# Center_Console_-_Inputs.net
KiCad netlist of a schematic drawn in Altium Designer
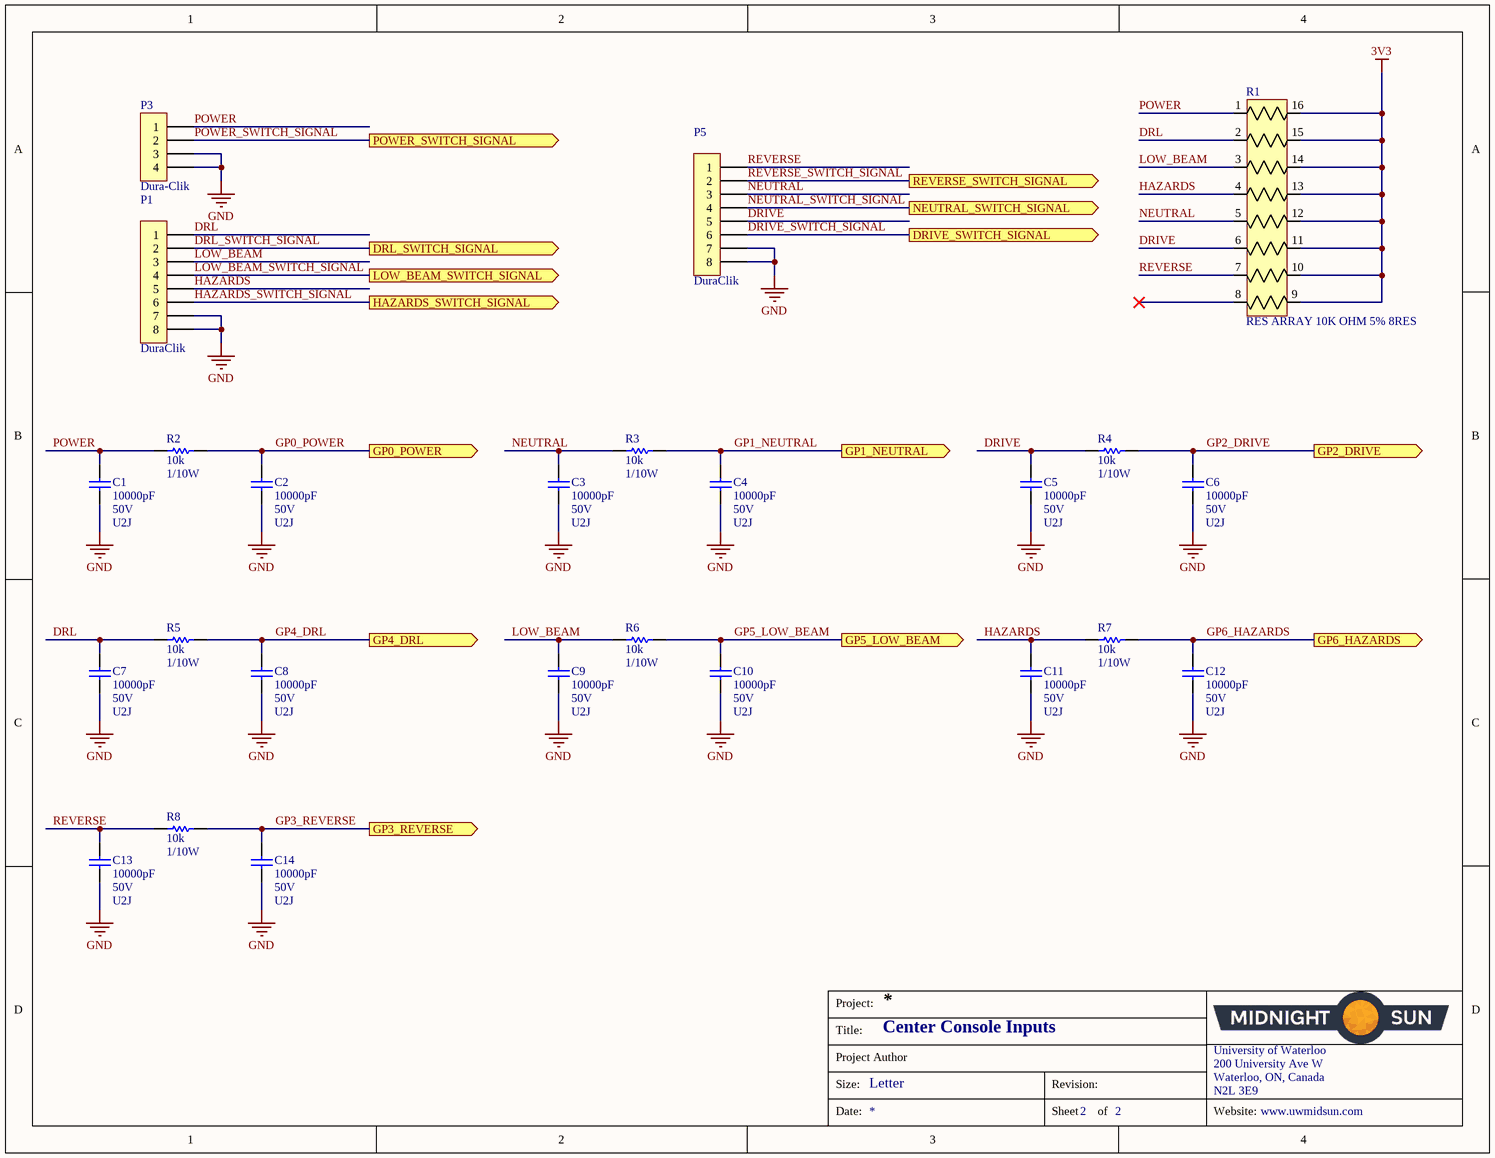
[diagram p0: Center Console - Inputs.SchDoc]

(export (version "E")
  (design (tool "Eeschema 10.0.6"))
  (components
    (comp (ref "C1")
      (value "CAP CER 10nF 50V 5% X7R 0603")
      (footprint "CAP, 0603")
      (description "10000pF ±5% 50V Ceramic Capacitor U2J 0603 (1608 Metric)")
      (fields
        (field (name "TOLERANCE") "±5%")
        (field (name "CAPACITANCE") "10000pF")
        (field (name "VOLTAGE") "50V")
        (field (name "TEMPERATURE COEFFICIENT") "U2J")
      )
      (libsource (lib "Schematic Diagrams") (part "CAP CER 10nF 50V 5% X7R 0603"))
    )
    (comp (ref "C2")
      (value "CAP CER 10nF 50V 5% X7R 0603")
      (footprint "CAP, 0603")
      (description "10000pF ±5% 50V Ceramic Capacitor U2J 0603 (1608 Metric)")
      (fields
        (field (name "TOLERANCE") "±5%")
        (field (name "CAPACITANCE") "10000pF")
        (field (name "VOLTAGE") "50V")
        (field (name "TEMPERATURE COEFFICIENT") "U2J")
      )
      (libsource (lib "Schematic Diagrams") (part "CAP CER 10nF 50V 5% X7R 0603"))
    )
    (comp (ref "C3")
      (value "CAP CER 10nF 50V 5% X7R 0603")
      (footprint "CAP, 0603")
      (description "10000pF ±5% 50V Ceramic Capacitor U2J 0603 (1608 Metric)")
      (fields
        (field (name "TOLERANCE") "±5%")
        (field (name "CAPACITANCE") "10000pF")
        (field (name "VOLTAGE") "50V")
        (field (name "TEMPERATURE COEFFICIENT") "U2J")
      )
      (libsource (lib "Schematic Diagrams") (part "CAP CER 10nF 50V 5% X7R 0603"))
    )
    (comp (ref "C4")
      (value "CAP CER 10nF 50V 5% X7R 0603")
      (footprint "CAP, 0603")
      (description "10000pF ±5% 50V Ceramic Capacitor U2J 0603 (1608 Metric)")
      (fields
        (field (name "TOLERANCE") "±5%")
        (field (name "CAPACITANCE") "10000pF")
        (field (name "VOLTAGE") "50V")
        (field (name "TEMPERATURE COEFFICIENT") "U2J")
      )
      (libsource (lib "Schematic Diagrams") (part "CAP CER 10nF 50V 5% X7R 0603"))
    )
    (comp (ref "C5")
      (value "CAP CER 10nF 50V 5% X7R 0603")
      (footprint "CAP, 0603")
      (description "10000pF ±5% 50V Ceramic Capacitor U2J 0603 (1608 Metric)")
      (fields
        (field (name "TOLERANCE") "±5%")
        (field (name "CAPACITANCE") "10000pF")
        (field (name "VOLTAGE") "50V")
        (field (name "TEMPERATURE COEFFICIENT") "U2J")
      )
      (libsource (lib "Schematic Diagrams") (part "CAP CER 10nF 50V 5% X7R 0603"))
    )
    (comp (ref "C6")
      (value "CAP CER 10nF 50V 5% X7R 0603")
      (footprint "CAP, 0603")
      (description "10000pF ±5% 50V Ceramic Capacitor U2J 0603 (1608 Metric)")
      (fields
        (field (name "TOLERANCE") "±5%")
        (field (name "CAPACITANCE") "10000pF")
        (field (name "VOLTAGE") "50V")
        (field (name "TEMPERATURE COEFFICIENT") "U2J")
      )
      (libsource (lib "Schematic Diagrams") (part "CAP CER 10nF 50V 5% X7R 0603"))
    )
    (comp (ref "C7")
      (value "CAP CER 10nF 50V 5% X7R 0603")
      (footprint "CAP, 0603")
      (description "10000pF ±5% 50V Ceramic Capacitor U2J 0603 (1608 Metric)")
      (fields
        (field (name "TOLERANCE") "±5%")
        (field (name "CAPACITANCE") "10000pF")
        (field (name "VOLTAGE") "50V")
        (field (name "TEMPERATURE COEFFICIENT") "U2J")
      )
      (libsource (lib "Schematic Diagrams") (part "CAP CER 10nF 50V 5% X7R 0603"))
    )
    (comp (ref "C8")
      (value "CAP CER 10nF 50V 5% X7R 0603")
      (footprint "CAP, 0603")
      (description "10000pF ±5% 50V Ceramic Capacitor U2J 0603 (1608 Metric)")
      (fields
        (field (name "TOLERANCE") "±5%")
        (field (name "CAPACITANCE") "10000pF")
        (field (name "VOLTAGE") "50V")
        (field (name "TEMPERATURE COEFFICIENT") "U2J")
      )
      (libsource (lib "Schematic Diagrams") (part "CAP CER 10nF 50V 5% X7R 0603"))
    )
    (comp (ref "C9")
      (value "CAP CER 10nF 50V 5% X7R 0603")
      (footprint "CAP, 0603")
      (description "10000pF ±5% 50V Ceramic Capacitor U2J 0603 (1608 Metric)")
      (fields
        (field (name "TOLERANCE") "±5%")
        (field (name "CAPACITANCE") "10000pF")
        (field (name "VOLTAGE") "50V")
        (field (name "TEMPERATURE COEFFICIENT") "U2J")
      )
      (libsource (lib "Schematic Diagrams") (part "CAP CER 10nF 50V 5% X7R 0603"))
    )
    (comp (ref "C10")
      (value "CAP CER 10nF 50V 5% X7R 0603")
      (footprint "CAP, 0603")
      (description "10000pF ±5% 50V Ceramic Capacitor U2J 0603 (1608 Metric)")
      (fields
        (field (name "TOLERANCE") "±5%")
        (field (name "CAPACITANCE") "10000pF")
        (field (name "VOLTAGE") "50V")
        (field (name "TEMPERATURE COEFFICIENT") "U2J")
      )
      (libsource (lib "Schematic Diagrams") (part "CAP CER 10nF 50V 5% X7R 0603"))
    )
    (comp (ref "C11")
      (value "CAP CER 10nF 50V 5% X7R 0603")
      (footprint "CAP, 0603")
      (description "10000pF ±5% 50V Ceramic Capacitor U2J 0603 (1608 Metric)")
      (fields
        (field (name "TOLERANCE") "±5%")
        (field (name "CAPACITANCE") "10000pF")
        (field (name "VOLTAGE") "50V")
        (field (name "TEMPERATURE COEFFICIENT") "U2J")
      )
      (libsource (lib "Schematic Diagrams") (part "CAP CER 10nF 50V 5% X7R 0603"))
    )
    (comp (ref "C12")
      (value "CAP CER 10nF 50V 5% X7R 0603")
      (footprint "CAP, 0603")
      (description "10000pF ±5% 50V Ceramic Capacitor U2J 0603 (1608 Metric)")
      (fields
        (field (name "TOLERANCE") "±5%")
        (field (name "CAPACITANCE") "10000pF")
        (field (name "VOLTAGE") "50V")
        (field (name "TEMPERATURE COEFFICIENT") "U2J")
      )
      (libsource (lib "Schematic Diagrams") (part "CAP CER 10nF 50V 5% X7R 0603"))
    )
    (comp (ref "C13")
      (value "CAP CER 10nF 50V 5% X7R 0603")
      (footprint "CAP, 0603")
      (description "10000pF ±5% 50V Ceramic Capacitor U2J 0603 (1608 Metric)")
      (fields
        (field (name "TOLERANCE") "±5%")
        (field (name "CAPACITANCE") "10000pF")
        (field (name "VOLTAGE") "50V")
        (field (name "TEMPERATURE COEFFICIENT") "U2J")
      )
      (libsource (lib "Schematic Diagrams") (part "CAP CER 10nF 50V 5% X7R 0603"))
    )
    (comp (ref "C14")
      (value "CAP CER 10nF 50V 5% X7R 0603")
      (footprint "CAP, 0603")
      (description "10000pF ±5% 50V Ceramic Capacitor U2J 0603 (1608 Metric)")
      (fields
        (field (name "TOLERANCE") "±5%")
        (field (name "CAPACITANCE") "10000pF")
        (field (name "VOLTAGE") "50V")
        (field (name "TEMPERATURE COEFFICIENT") "U2J")
      )
      (libsource (lib "Schematic Diagrams") (part "CAP CER 10nF 50V 5% X7R 0603"))
    )
    (comp (ref "P1")
      (value "CONN 8POS DURA-CLIK 0.079\"")
      (footprint "CONN, 8POS Dura-Clik")
      (description "8 Positions Header Connector 0.079\" (2.00mm) Surface Mount Tin")
      (fields (field (name "SERIES") "DuraClik"))
      (libsource (lib "Schematic Diagrams") (part "CONN 8POS DURA-CLIK 0.079{dblquote}"))
    )
    (comp (ref "P3")
      (value "Dura-Clik")
      (footprint "CONN, 4POS DURA-CLIK VERT")
      (description "4 Positions Header Connector 0.079\" (2.00mm) Surface Mount Tin")
      (fields
        (field (name "MANUFACTURER") "Molex, LLC")
        (field (name "MANUFACTURER PART NUMBER") "5600200420")
      )
      (libsource (lib "Schematic Diagrams") (part "CONN 4POS DURA-CLIK 0.079{dblquote}"))
    )
    (comp (ref "P5")
      (value "CONN 8POS DURA-CLIK 0.079\"")
      (footprint "CONN, 8POS Dura-Clik")
      (description "8 Positions Header Connector 0.079\" (2.00mm) Surface Mount Tin")
      (fields (field (name "SERIES") "DuraClik"))
      (libsource (lib "Schematic Diagrams") (part "CONN 8POS DURA-CLIK 0.079{dblquote}"))
    )
    (comp (ref "R1")
      (value "RES ARRAY 10K OHM 5% 8RES")
      (footprint "RES ARRAY, 8 POS 1506")
      (description "RES ARRAY SMD 10K 5% 62.5mW 1506")
      (fields
        (field (name "MANUFACTURER_PART_NUMBER") "EXB-2HV103JV")
        (field (name "MANUFACTURER") "Panasonic Electronic Components")
        (field (name "COPYRIGHT") "Copyright (C) 2015 Accelerated Designs. All rights reserved")
      )
      (libsource (lib "Schematic Diagrams") (part "RES ARRAY 10K OHM 5% 8RES EXB-2HV103JV"))
    )
    (comp (ref "R2")
      (value "RES 10K OHM 1% 1/10W 0603")
      (footprint "RES, 0603")
      (description "RES SMD 10K OHM 1% 1/10W 0603")
      (fields
        (field (name "TOLERANCE") "±1%")
        (field (name "RESISTANCE") "10k")
        (field (name "POWER") "1/10W")
      )
      (libsource (lib "Schematic Diagrams") (part "RES 10K OHM 1% 1/10W 0603"))
    )
    (comp (ref "R3")
      (value "RES 10K OHM 1% 1/10W 0603")
      (footprint "RES, 0603")
      (description "RES SMD 10K OHM 1% 1/10W 0603")
      (fields
        (field (name "TOLERANCE") "±1%")
        (field (name "RESISTANCE") "10k")
        (field (name "POWER") "1/10W")
      )
      (libsource (lib "Schematic Diagrams") (part "RES 10K OHM 1% 1/10W 0603"))
    )
    (comp (ref "R4")
      (value "RES 10K OHM 1% 1/10W 0603")
      (footprint "RES, 0603")
      (description "RES SMD 10K OHM 1% 1/10W 0603")
      (fields
        (field (name "TOLERANCE") "±1%")
        (field (name "RESISTANCE") "10k")
        (field (name "POWER") "1/10W")
      )
      (libsource (lib "Schematic Diagrams") (part "RES 10K OHM 1% 1/10W 0603"))
    )
    (comp (ref "R5")
      (value "RES 10K OHM 1% 1/10W 0603")
      (footprint "RES, 0603")
      (description "RES SMD 10K OHM 1% 1/10W 0603")
      (fields
        (field (name "TOLERANCE") "±1%")
        (field (name "RESISTANCE") "10k")
        (field (name "POWER") "1/10W")
      )
      (libsource (lib "Schematic Diagrams") (part "RES 10K OHM 1% 1/10W 0603"))
    )
    (comp (ref "R6")
      (value "RES 10K OHM 1% 1/10W 0603")
      (footprint "RES, 0603")
      (description "RES SMD 10K OHM 1% 1/10W 0603")
      (fields
        (field (name "TOLERANCE") "±1%")
        (field (name "RESISTANCE") "10k")
        (field (name "POWER") "1/10W")
      )
      (libsource (lib "Schematic Diagrams") (part "RES 10K OHM 1% 1/10W 0603"))
    )
    (comp (ref "R7")
      (value "RES 10K OHM 1% 1/10W 0603")
      (footprint "RES, 0603")
      (description "RES SMD 10K OHM 1% 1/10W 0603")
      (fields
        (field (name "TOLERANCE") "±1%")
        (field (name "RESISTANCE") "10k")
        (field (name "POWER") "1/10W")
      )
      (libsource (lib "Schematic Diagrams") (part "RES 10K OHM 1% 1/10W 0603"))
    )
    (comp (ref "R8")
      (value "RES 10K OHM 1% 1/10W 0603")
      (footprint "RES, 0603")
      (description "RES SMD 10K OHM 1% 1/10W 0603")
      (fields
        (field (name "TOLERANCE") "±1%")
        (field (name "RESISTANCE") "10k")
        (field (name "POWER") "1/10W")
      )
      (libsource (lib "Schematic Diagrams") (part "RES 10K OHM 1% 1/10W 0603"))
    )
  )
  (nets
    (net (code "1") (name "/DRIVE") (class "Default")
      (node (ref "C5") (pin "1") (pinfunction "1_1") (pintype "passive"))
      (node (ref "P5") (pin "5") (pinfunction "5_5") (pintype "passive"))
      (node (ref "R1") (pin "6") (pinfunction "6_6") (pintype "passive"))
      (node (ref "R4") (pin "1") (pinfunction "1_1") (pintype "passive"))
    )
    (net (code "2") (name "/DRIVE_SWITCH_SIGNAL") (class "Default")
      (node (ref "P5") (pin "6") (pinfunction "6_6") (pintype "passive"))
    )
    (net (code "3") (name "/DRL") (class "Default")
      (node (ref "C7") (pin "1") (pinfunction "1_1") (pintype "passive"))
      (node (ref "P1") (pin "1") (pinfunction "1_1") (pintype "passive"))
      (node (ref "R1") (pin "2") (pinfunction "2_2") (pintype "passive"))
      (node (ref "R5") (pin "1") (pinfunction "1_1") (pintype "passive"))
    )
    (net (code "4") (name "/DRL_SWITCH_SIGNAL") (class "Default")
      (node (ref "P1") (pin "2") (pinfunction "2_2") (pintype "passive"))
    )
    (net (code "5") (name "/GP0_POWER") (class "Default")
      (node (ref "C2") (pin "1") (pinfunction "1_1") (pintype "passive"))
      (node (ref "R2") (pin "2") (pinfunction "2_2") (pintype "passive"))
    )
    (net (code "6") (name "/GP1_NEUTRAL") (class "Default")
      (node (ref "C4") (pin "1") (pinfunction "1_1") (pintype "passive"))
      (node (ref "R3") (pin "2") (pinfunction "2_2") (pintype "passive"))
    )
    (net (code "7") (name "/GP2_DRIVE") (class "Default")
      (node (ref "C6") (pin "1") (pinfunction "1_1") (pintype "passive"))
      (node (ref "R4") (pin "2") (pinfunction "2_2") (pintype "passive"))
    )
    (net (code "8") (name "/GP3_REVERSE") (class "Default")
      (node (ref "C14") (pin "1") (pinfunction "1_1") (pintype "passive"))
      (node (ref "R8") (pin "2") (pinfunction "2_2") (pintype "passive"))
    )
    (net (code "9") (name "/GP4_DRL") (class "Default")
      (node (ref "C8") (pin "1") (pinfunction "1_1") (pintype "passive"))
      (node (ref "R5") (pin "2") (pinfunction "2_2") (pintype "passive"))
    )
    (net (code "10") (name "/GP5_LOW_BEAM") (class "Default")
      (node (ref "C10") (pin "1") (pinfunction "1_1") (pintype "passive"))
      (node (ref "R6") (pin "2") (pinfunction "2_2") (pintype "passive"))
    )
    (net (code "11") (name "/GP6_HAZARDS") (class "Default")
      (node (ref "C12") (pin "1") (pinfunction "1_1") (pintype "passive"))
      (node (ref "R7") (pin "2") (pinfunction "2_2") (pintype "passive"))
    )
    (net (code "12") (name "/HAZARDS") (class "Default")
      (node (ref "C11") (pin "1") (pinfunction "1_1") (pintype "passive"))
      (node (ref "P1") (pin "5") (pinfunction "5_5") (pintype "passive"))
      (node (ref "R1") (pin "4") (pinfunction "4_4") (pintype "passive"))
      (node (ref "R7") (pin "1") (pinfunction "1_1") (pintype "passive"))
    )
    (net (code "13") (name "/HAZARDS_SWITCH_SIGNAL") (class "Default")
      (node (ref "P1") (pin "6") (pinfunction "6_6") (pintype "passive"))
    )
    (net (code "14") (name "/LOW_BEAM") (class "Default")
      (node (ref "C9") (pin "1") (pinfunction "1_1") (pintype "passive"))
      (node (ref "P1") (pin "3") (pinfunction "3_3") (pintype "passive"))
      (node (ref "R1") (pin "3") (pinfunction "3_3") (pintype "passive"))
      (node (ref "R6") (pin "1") (pinfunction "1_1") (pintype "passive"))
    )
    (net (code "15") (name "/LOW_BEAM_SWITCH_SIGNAL") (class "Default")
      (node (ref "P1") (pin "4") (pinfunction "4_4") (pintype "passive"))
    )
    (net (code "16") (name "/NEUTRAL") (class "Default")
      (node (ref "C3") (pin "1") (pinfunction "1_1") (pintype "passive"))
      (node (ref "P5") (pin "3") (pinfunction "3_3") (pintype "passive"))
      (node (ref "R1") (pin "5") (pinfunction "5_5") (pintype "passive"))
      (node (ref "R3") (pin "1") (pinfunction "1_1") (pintype "passive"))
    )
    (net (code "17") (name "/NEUTRAL_SWITCH_SIGNAL") (class "Default")
      (node (ref "P5") (pin "4") (pinfunction "4_4") (pintype "passive"))
    )
    (net (code "18") (name "/POWER") (class "Default")
      (node (ref "C1") (pin "1") (pinfunction "1_1") (pintype "passive"))
      (node (ref "P3") (pin "1") (pinfunction "1_1") (pintype "passive"))
      (node (ref "R1") (pin "1") (pinfunction "1_1") (pintype "passive"))
      (node (ref "R2") (pin "1") (pinfunction "1_1") (pintype "passive"))
    )
    (net (code "19") (name "/POWER_SWITCH_SIGNAL") (class "Default")
      (node (ref "P3") (pin "2") (pinfunction "2_2") (pintype "passive"))
    )
    (net (code "20") (name "/REVERSE") (class "Default")
      (node (ref "C13") (pin "1") (pinfunction "1_1") (pintype "passive"))
      (node (ref "P5") (pin "1") (pinfunction "1_1") (pintype "passive"))
      (node (ref "R1") (pin "7") (pinfunction "7_7") (pintype "passive"))
      (node (ref "R8") (pin "1") (pinfunction "1_1") (pintype "passive"))
    )
    (net (code "21") (name "/REVERSE_SWITCH_SIGNAL") (class "Default")
      (node (ref "P5") (pin "2") (pinfunction "2_2") (pintype "passive"))
    )
    (net (code "22") (name "3V3") (class "Default")
      (node (ref "R1") (pin "10") (pinfunction "10_10") (pintype "passive"))
      (node (ref "R1") (pin "11") (pinfunction "11_11") (pintype "passive"))
      (node (ref "R1") (pin "12") (pinfunction "12_12") (pintype "passive"))
      (node (ref "R1") (pin "13") (pinfunction "13_13") (pintype "passive"))
      (node (ref "R1") (pin "14") (pinfunction "14_14") (pintype "passive"))
      (node (ref "R1") (pin "15") (pinfunction "15_15") (pintype "passive"))
      (node (ref "R1") (pin "16") (pinfunction "16_16") (pintype "passive"))
      (node (ref "R1") (pin "9") (pinfunction "9_9") (pintype "passive"))
    )
    (net (code "23") (name "GND") (class "Default")
      (node (ref "C1") (pin "2") (pinfunction "2_2") (pintype "passive"))
      (node (ref "C10") (pin "2") (pinfunction "2_2") (pintype "passive"))
      (node (ref "C11") (pin "2") (pinfunction "2_2") (pintype "passive"))
      (node (ref "C12") (pin "2") (pinfunction "2_2") (pintype "passive"))
      (node (ref "C13") (pin "2") (pinfunction "2_2") (pintype "passive"))
      (node (ref "C14") (pin "2") (pinfunction "2_2") (pintype "passive"))
      (node (ref "C2") (pin "2") (pinfunction "2_2") (pintype "passive"))
      (node (ref "C3") (pin "2") (pinfunction "2_2") (pintype "passive"))
      (node (ref "C4") (pin "2") (pinfunction "2_2") (pintype "passive"))
      (node (ref "C5") (pin "2") (pinfunction "2_2") (pintype "passive"))
      (node (ref "C6") (pin "2") (pinfunction "2_2") (pintype "passive"))
      (node (ref "C7") (pin "2") (pinfunction "2_2") (pintype "passive"))
      (node (ref "C8") (pin "2") (pinfunction "2_2") (pintype "passive"))
      (node (ref "C9") (pin "2") (pinfunction "2_2") (pintype "passive"))
      (node (ref "P1") (pin "7") (pinfunction "7_7") (pintype "passive"))
      (node (ref "P1") (pin "8") (pinfunction "8_8") (pintype "passive"))
      (node (ref "P3") (pin "3") (pinfunction "3_3") (pintype "passive"))
      (node (ref "P3") (pin "4") (pinfunction "4_4") (pintype "passive"))
      (node (ref "P5") (pin "7") (pinfunction "7_7") (pintype "passive"))
      (node (ref "P5") (pin "8") (pinfunction "8_8") (pintype "passive"))
    )
    (net (code "24") (name "unconnected-(R1-Pad8)") (class "Default")
      (node (ref "R1") (pin "8") (pinfunction "8_8") (pintype "passive+no_connect"))
    )
  )
)
